# CONNECTORS.net
KiCad netlist of a schematic drawn in Altium Designer
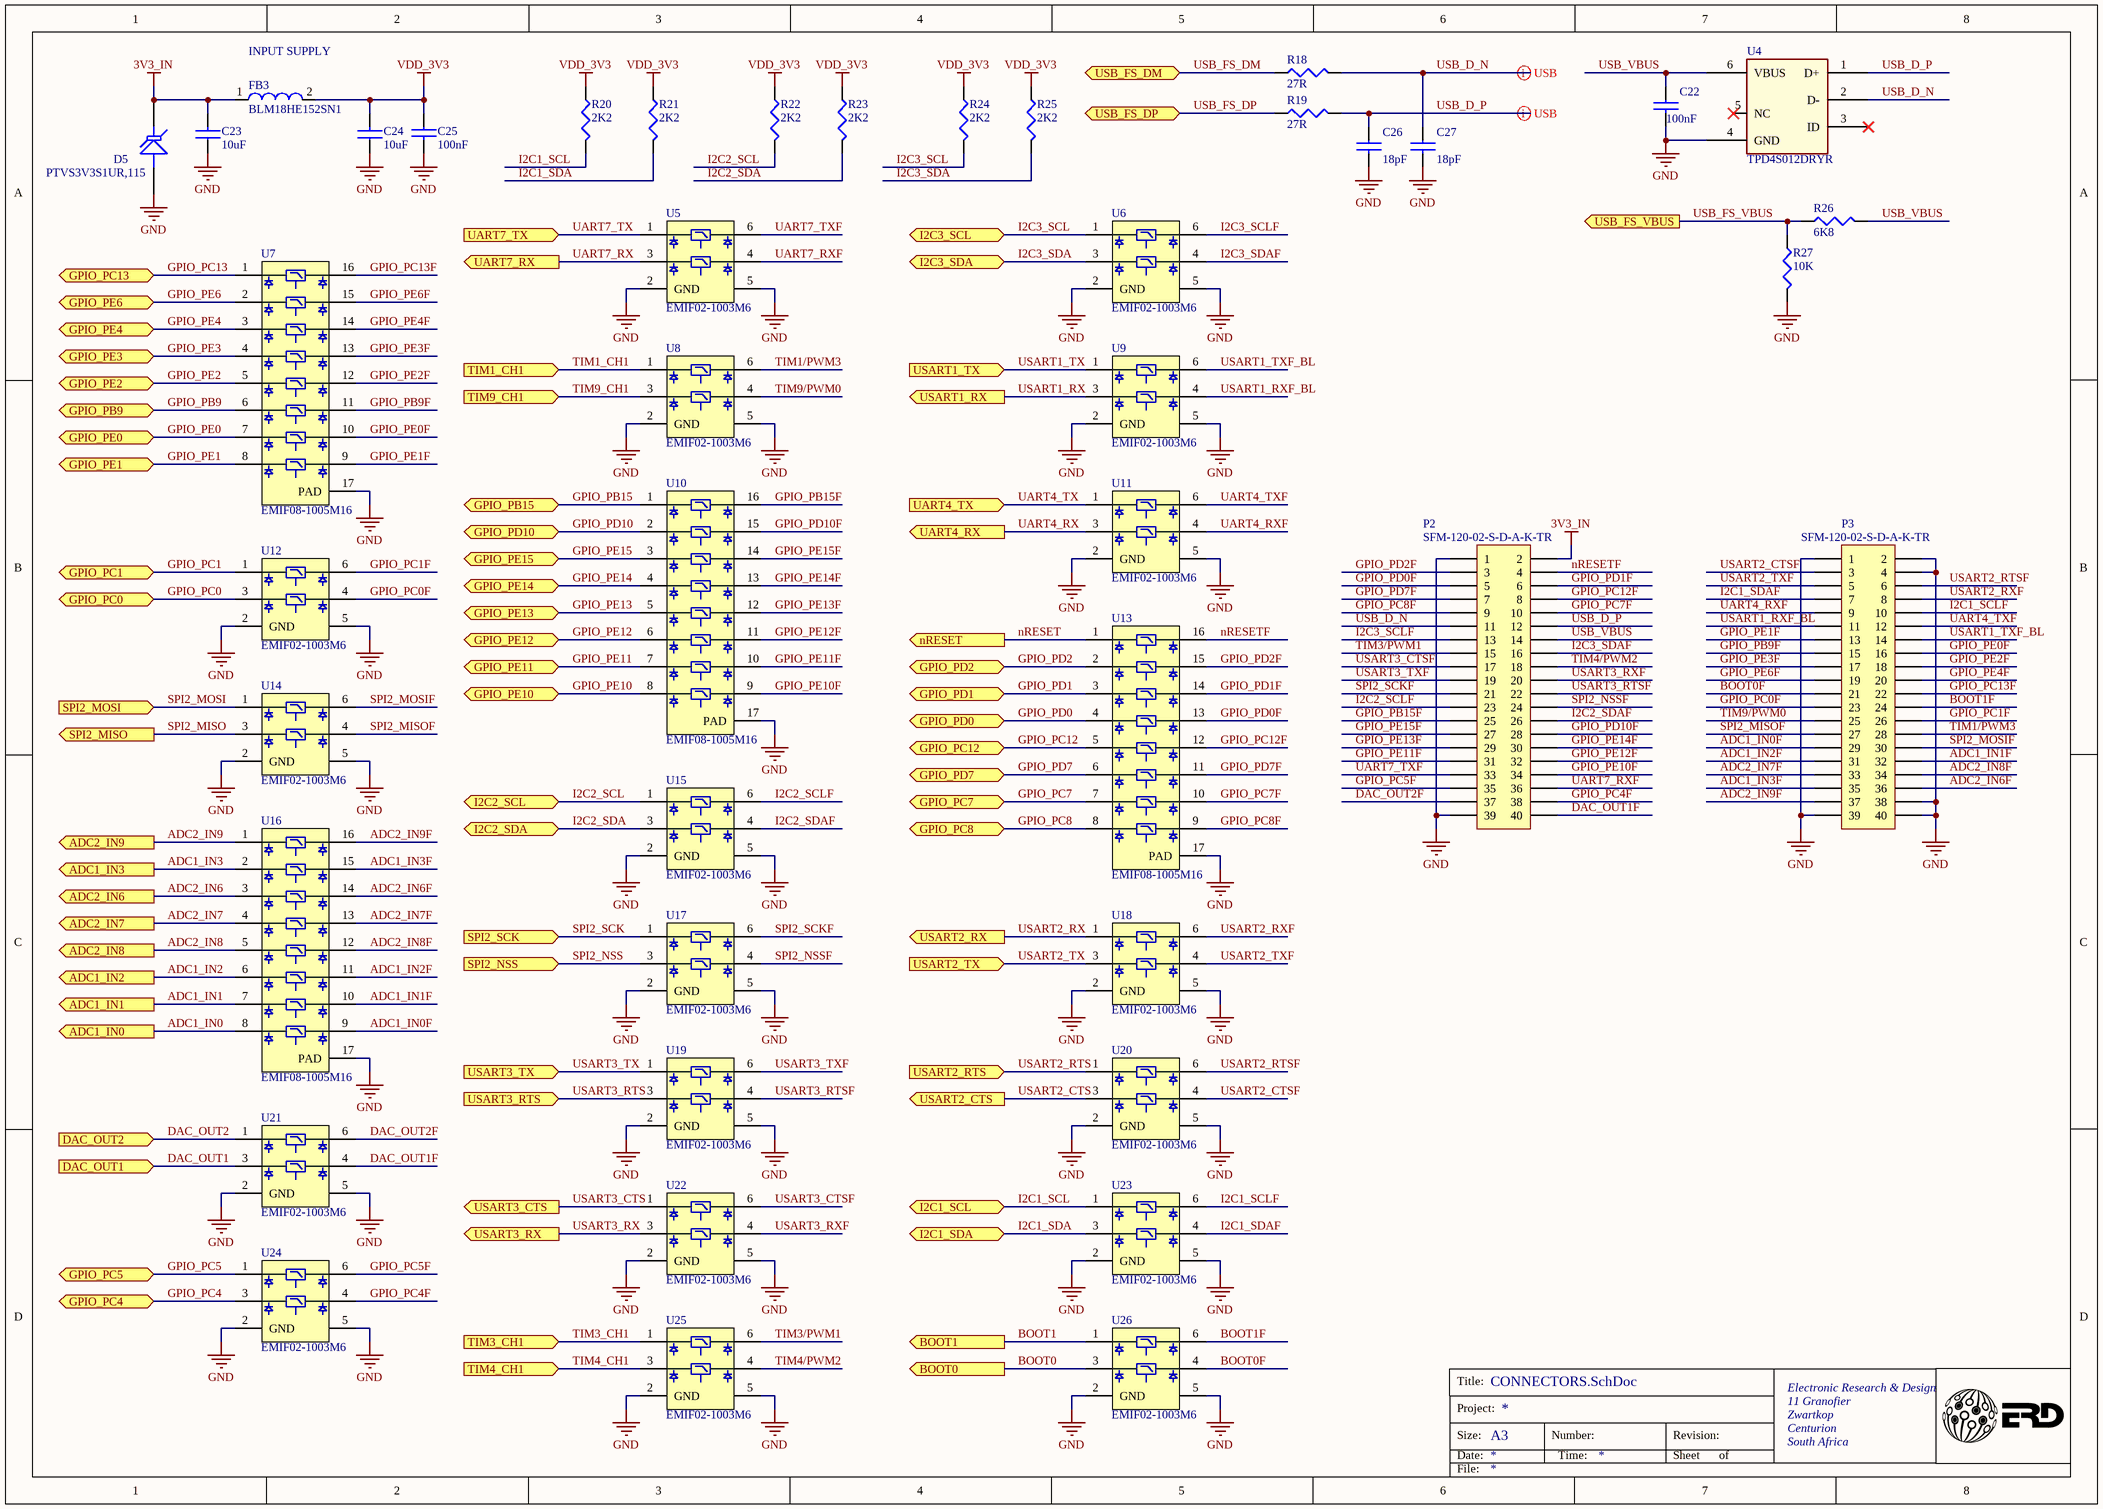
[diagram p0: CONNECTORS.SchDoc]

(export (version "E")
  (design (tool "Eeschema 10.0.6"))
  (components
    (comp (ref "C22")
      (value "100nF")
      (footprint "CC0402")
      (description "CAP CER 0.1UF 50V 10% X7R 0402")
      (fields (field (name "MANUFACTURER") "Murata") (field (name "PARTNUMBER") "GCM155R71H104KE02D"))
      (libsource (lib "ERD TiAm") (part "CAP CER 0.1UF 10V 10% X5R 0402"))
    )
    (comp (ref "C23")
      (value "10uF")
      (footprint "CC0603")
      (description "CAP CER 10UF 25V 20% X5R 0603")
      (fields (field (name "MANUFACTURER") "Murata") (field (name "PARTNUMBER") "GRM188R61E106MA73D"))
      (libsource (lib "ERD TiAm") (part "CAP CER 0.1UF 10V 10% X5R 0402"))
    )
    (comp (ref "C24")
      (value "10uF")
      (footprint "CC0603")
      (description "CAP CER 10UF 25V 20% X5R 0603")
      (fields (field (name "MANUFACTURER") "Murata") (field (name "PARTNUMBER") "GRM188R61E106MA73D"))
      (libsource (lib "ERD TiAm") (part "CAP CER 0.1UF 10V 10% X5R 0402"))
    )
    (comp (ref "C25")
      (value "100nF")
      (footprint "CC0402")
      (description "CAP CER 0.1UF 50V 10% X7R 0402")
      (fields (field (name "MANUFACTURER") "Murata") (field (name "PARTNUMBER") "GCM155R71H104KE02D"))
      (libsource (lib "ERD TiAm") (part "CAP CER 0.1UF 10V 10% X5R 0402"))
    )
    (comp (ref "C26")
      (value "18pF")
      (footprint "CC0402")
      (description "CAP CER 18pF 50V 5% C0G 0402")
      (fields (field (name "MANUFACTURER") "AVX") (field (name "PARTNUMBER") "GJM1555C1H180FB01D"))
      (libsource (lib "ERD TiAm") (part "CAP CER 2.2UF 6.3V 10% X5R 0402"))
    )
    (comp (ref "C27")
      (value "18pF")
      (footprint "CC0402")
      (description "CAP CER 18pF 50V 5% C0G 0402")
      (fields (field (name "MANUFACTURER") "AVX") (field (name "PARTNUMBER") "GJM1555C1H180FB01D"))
      (libsource (lib "ERD TiAm") (part "CAP CER 2.2UF 6.3V 10% X5R 0402"))
    )
    (comp (ref "D5")
      (value "PTVS3V3S1UR,115")
      (footprint "SOD123W")
      (description "TVS, 3V3")
      (libsource (lib "Miscellaneous Devices") (part "Tranzorb"))
    )
    (comp (ref "FB3")
      (value "BLM18HE152SN1")
      (footprint "LC0603")
      (description "FERRITE, 500mA, 500mOHM, 0603")
      (libsource (lib "BEAGLEBONEBLACK_REV A5B") (part "FER_180_200_0"))
    )
    (comp (ref "P2")
      (value "SFM-120-02-S-D-A-K-TR")
      (footprint "ERD TiAm:SFM-120-02-S-D-A-K-TR")
      (description "Receptacle, 40 POS, 1.27mm PITCH, SMD")
      (libsource (lib "Miscellaneous Connectors") (part "Header 20X2"))
    )
    (comp (ref "P3")
      (value "SFM-120-02-S-D-A-K-TR")
      (footprint "ERD TiAm:SFM-120-02-S-D-A-K-TR")
      (description "Receptacle, 40 POS, 1.27mm PITCH, SMD")
      (libsource (lib "Miscellaneous Connectors") (part "Header 20X2"))
    )
    (comp (ref "R18")
      (value "27R")
      (footprint "RC0402")
      (description "RES, 27 OHM, 1/16W, 1%, 0402")
      (fields (field (name "MANUFACTURER") "Yageo") (field (name "PARTNUMBER") "RC0402FR-0727RL"))
      (libsource (lib "ERD TiAm") (part "RES_10K_1/16W_1%_0402"))
    )
    (comp (ref "R19")
      (value "27R")
      (footprint "RC0402")
      (description "RES, 27 OHM, 1/16W, 1%, 0402")
      (fields (field (name "MANUFACTURER") "Yageo") (field (name "PARTNUMBER") "RC0402FR-0727RL"))
      (libsource (lib "ERD TiAm") (part "RES_10K_1/16W_1%_0402"))
    )
    (comp (ref "R20")
      (value "2K2")
      (footprint "RC0402")
      (description "RES, 2K2 OHM, 1/16W, 1%, 0402")
      (fields (field (name "MANUFACTURER") "Yageo") (field (name "PARTNUMBER") "RC0402FR-072K2L"))
      (libsource (lib "ERD TiAm") (part "RES_10K_1/16W_1%_0402"))
    )
    (comp (ref "R21")
      (value "2K2")
      (footprint "RC0402")
      (description "RES, 2K2 OHM, 1/16W, 1%, 0402")
      (fields (field (name "MANUFACTURER") "Yageo") (field (name "PARTNUMBER") "RC0402FR-072K2L"))
      (libsource (lib "ERD TiAm") (part "RES_10K_1/16W_1%_0402"))
    )
    (comp (ref "R22")
      (value "2K2")
      (footprint "RC0402")
      (description "RES, 2K2 OHM, 1/16W, 1%, 0402")
      (fields (field (name "MANUFACTURER") "Yageo") (field (name "PARTNUMBER") "RC0402FR-072K2L"))
      (libsource (lib "ERD TiAm") (part "RES_10K_1/16W_1%_0402"))
    )
    (comp (ref "R23")
      (value "2K2")
      (footprint "RC0402")
      (description "RES, 2K2 OHM, 1/16W, 1%, 0402")
      (fields (field (name "MANUFACTURER") "Yageo") (field (name "PARTNUMBER") "RC0402FR-072K2L"))
      (libsource (lib "ERD TiAm") (part "RES_10K_1/16W_1%_0402"))
    )
    (comp (ref "R24")
      (value "2K2")
      (footprint "RC0402")
      (description "RES, 2K2 OHM, 1/16W, 1%, 0402")
      (fields (field (name "MANUFACTURER") "Yageo") (field (name "PARTNUMBER") "RC0402FR-072K2L"))
      (libsource (lib "ERD TiAm") (part "RES_10K_1/16W_1%_0402"))
    )
    (comp (ref "R25")
      (value "2K2")
      (footprint "RC0402")
      (description "RES, 2K2 OHM, 1/16W, 1%, 0402")
      (fields (field (name "MANUFACTURER") "Yageo") (field (name "PARTNUMBER") "RC0402FR-072K2L"))
      (libsource (lib "ERD TiAm") (part "RES_10K_1/16W_1%_0402"))
    )
    (comp (ref "R26")
      (value "6K8")
      (footprint "RC0402")
      (description "RES, 6K8 OHM, 1/16W, 1%, 0402")
      (fields (field (name "MANUFACTURER") "Yageo") (field (name "PARTNUMBER") "RC0402FR-076K8L"))
      (libsource (lib "ERD TiAm") (part "RES_10K_1/16W_1%_0402"))
    )
    (comp (ref "R27")
      (value "10K")
      (footprint "RC0402")
      (description "RES, 10K OHM, 1/16W, 1%, 0402")
      (fields (field (name "MANUFACTURER") "Yageo") (field (name "PARTNUMBER") "RC0402FR-0710KL"))
      (libsource (lib "ERD TiAm") (part "RES_10K_1/16W_1%_0402"))
    )
    (comp (ref "U4")
      (value "TPD4S012DRYR")
      (footprint "U_6_DRY")
      (description "ESD 4channel USB Interface")
      (fields (field (name "MANUFACTURER") "Texas Instruments"))
      (libsource (lib "ERD TiAm") (part "PROT_TPD4S012"))
    )
    (comp (ref "U5")
      (value "EMIF02-1003M6")
      (footprint "uQFN-6L")
      (description "EMI Filter, ESD, uQFN-6")
      (libsource (lib "ERD TiAm") (part "EMIF02-1003M6"))
    )
    (comp (ref "U6")
      (value "EMIF02-1003M6")
      (footprint "uQFN-6L")
      (description "EMI Filter, ESD, uQFN-6")
      (libsource (lib "ERD TiAm") (part "EMIF02-1003M6"))
    )
    (comp (ref "U7")
      (value "EMIF08-1005M16")
      (footprint "QFN-16L")
      (description "EMI Filter, ESD, QFN-16L")
      (libsource (lib "ERD TiAm") (part "EMIF08-1005M16"))
    )
    (comp (ref "U8")
      (value "EMIF02-1003M6")
      (footprint "uQFN-6L")
      (description "EMI Filter, ESD, uQFN-6")
      (libsource (lib "ERD TiAm") (part "EMIF02-1003M6"))
    )
    (comp (ref "U9")
      (value "EMIF02-1003M6")
      (footprint "uQFN-6L")
      (description "EMI Filter, ESD, uQFN-6")
      (libsource (lib "ERD TiAm") (part "EMIF02-1003M6"))
    )
    (comp (ref "U10")
      (value "EMIF08-1005M16")
      (footprint "QFN-16L")
      (description "EMI Filter, ESD, QFN-16L")
      (libsource (lib "ERD TiAm") (part "EMIF08-1005M16"))
    )
    (comp (ref "U11")
      (value "EMIF02-1003M6")
      (footprint "uQFN-6L")
      (description "EMI Filter, ESD, uQFN-6")
      (libsource (lib "ERD TiAm") (part "EMIF02-1003M6"))
    )
    (comp (ref "U12")
      (value "EMIF02-1003M6")
      (footprint "uQFN-6L")
      (description "EMI Filter, ESD, uQFN-6")
      (libsource (lib "ERD TiAm") (part "EMIF02-1003M6"))
    )
    (comp (ref "U13")
      (value "EMIF08-1005M16")
      (footprint "QFN-16L")
      (description "EMI Filter, ESD, QFN-16L")
      (libsource (lib "ERD TiAm") (part "EMIF08-1005M16"))
    )
    (comp (ref "U14")
      (value "EMIF02-1003M6")
      (footprint "uQFN-6L")
      (description "EMI Filter, ESD, uQFN-6")
      (libsource (lib "ERD TiAm") (part "EMIF02-1003M6"))
    )
    (comp (ref "U15")
      (value "EMIF02-1003M6")
      (footprint "uQFN-6L")
      (description "EMI Filter, ESD, uQFN-6")
      (libsource (lib "ERD TiAm") (part "EMIF02-1003M6"))
    )
    (comp (ref "U16")
      (value "EMIF08-1005M16")
      (footprint "QFN-16L")
      (description "EMI Filter, ESD, QFN-16L")
      (libsource (lib "ERD TiAm") (part "EMIF08-1005M16"))
    )
    (comp (ref "U17")
      (value "EMIF02-1003M6")
      (footprint "uQFN-6L")
      (description "EMI Filter, ESD, uQFN-6")
      (libsource (lib "ERD TiAm") (part "EMIF02-1003M6"))
    )
    (comp (ref "U18")
      (value "EMIF02-1003M6")
      (footprint "uQFN-6L")
      (description "EMI Filter, ESD, uQFN-6")
      (libsource (lib "ERD TiAm") (part "EMIF02-1003M6"))
    )
    (comp (ref "U19")
      (value "EMIF02-1003M6")
      (footprint "uQFN-6L")
      (description "EMI Filter, ESD, uQFN-6")
      (libsource (lib "ERD TiAm") (part "EMIF02-1003M6"))
    )
    (comp (ref "U20")
      (value "EMIF02-1003M6")
      (footprint "uQFN-6L")
      (description "EMI Filter, ESD, uQFN-6")
      (libsource (lib "ERD TiAm") (part "EMIF02-1003M6"))
    )
    (comp (ref "U21")
      (value "EMIF02-1003M6")
      (footprint "uQFN-6L")
      (description "EMI Filter, ESD, uQFN-6")
      (libsource (lib "ERD TiAm") (part "EMIF02-1003M6"))
    )
    (comp (ref "U22")
      (value "EMIF02-1003M6")
      (footprint "uQFN-6L")
      (description "EMI Filter, ESD, uQFN-6")
      (libsource (lib "ERD TiAm") (part "EMIF02-1003M6"))
    )
    (comp (ref "U23")
      (value "EMIF02-1003M6")
      (footprint "uQFN-6L")
      (description "EMI Filter, ESD, uQFN-6")
      (libsource (lib "ERD TiAm") (part "EMIF02-1003M6"))
    )
    (comp (ref "U24")
      (value "EMIF02-1003M6")
      (footprint "uQFN-6L")
      (description "EMI Filter, ESD, uQFN-6")
      (libsource (lib "ERD TiAm") (part "EMIF02-1003M6"))
    )
    (comp (ref "U25")
      (value "EMIF02-1003M6")
      (footprint "uQFN-6L")
      (description "EMI Filter, ESD, uQFN-6")
      (libsource (lib "ERD TiAm") (part "EMIF02-1003M6"))
    )
    (comp (ref "U26")
      (value "EMIF02-1003M6")
      (footprint "uQFN-6L")
      (description "EMI Filter, ESD, uQFN-6")
      (libsource (lib "ERD TiAm") (part "EMIF02-1003M6"))
    )
  )
  (nets
    (net (code "1") (name "/ADC1_IN0") (class "Default")
      (node (ref "U16") (pin "8") (pinfunction "8_8") (pintype "passive"))
    )
    (net (code "2") (name "/ADC1_IN0F") (class "Default")
      (node (ref "P3") (pin "29") (pinfunction "29_29") (pintype "passive"))
      (node (ref "U16") (pin "9") (pinfunction "9_9") (pintype "passive"))
    )
    (net (code "3") (name "/ADC1_IN1") (class "Default")
      (node (ref "U16") (pin "7") (pinfunction "7_7") (pintype "passive"))
    )
    (net (code "4") (name "/ADC1_IN1F") (class "Default")
      (node (ref "P3") (pin "32") (pinfunction "32_32") (pintype "passive"))
      (node (ref "U16") (pin "10") (pinfunction "10_10") (pintype "passive"))
    )
    (net (code "5") (name "/ADC1_IN2") (class "Default")
      (node (ref "U16") (pin "6") (pinfunction "6_6") (pintype "passive"))
    )
    (net (code "6") (name "/ADC1_IN2F") (class "Default")
      (node (ref "P3") (pin "31") (pinfunction "31_31") (pintype "passive"))
      (node (ref "U16") (pin "11") (pinfunction "11_11") (pintype "passive"))
    )
    (net (code "7") (name "/ADC1_IN3") (class "Default")
      (node (ref "U16") (pin "2") (pinfunction "2_2") (pintype "passive"))
    )
    (net (code "8") (name "/ADC1_IN3F") (class "Default")
      (node (ref "P3") (pin "35") (pinfunction "35_35") (pintype "passive"))
      (node (ref "U16") (pin "15") (pinfunction "15_15") (pintype "passive"))
    )
    (net (code "9") (name "/ADC2_IN6") (class "Default")
      (node (ref "U16") (pin "3") (pinfunction "3_3") (pintype "passive"))
    )
    (net (code "10") (name "/ADC2_IN6F") (class "Default")
      (node (ref "P3") (pin "36") (pinfunction "36_36") (pintype "passive"))
      (node (ref "U16") (pin "14") (pinfunction "14_14") (pintype "passive"))
    )
    (net (code "11") (name "/ADC2_IN7") (class "Default")
      (node (ref "U16") (pin "4") (pinfunction "4_4") (pintype "passive"))
    )
    (net (code "12") (name "/ADC2_IN7F") (class "Default")
      (node (ref "P3") (pin "33") (pinfunction "33_33") (pintype "passive"))
      (node (ref "U16") (pin "13") (pinfunction "13_13") (pintype "passive"))
    )
    (net (code "13") (name "/ADC2_IN8") (class "Default")
      (node (ref "U16") (pin "5") (pinfunction "5_5") (pintype "passive"))
    )
    (net (code "14") (name "/ADC2_IN8F") (class "Default")
      (node (ref "P3") (pin "34") (pinfunction "34_34") (pintype "passive"))
      (node (ref "U16") (pin "12") (pinfunction "12_12") (pintype "passive"))
    )
    (net (code "15") (name "/ADC2_IN9") (class "Default")
      (node (ref "U16") (pin "1") (pinfunction "1_1") (pintype "passive"))
    )
    (net (code "16") (name "/ADC2_IN9F") (class "Default")
      (node (ref "P3") (pin "37") (pinfunction "37_37") (pintype "passive"))
      (node (ref "U16") (pin "16") (pinfunction "16_16") (pintype "passive"))
    )
    (net (code "17") (name "/BOOT0") (class "Default")
      (node (ref "U26") (pin "3") (pinfunction "3_3") (pintype "passive"))
    )
    (net (code "18") (name "/BOOT0F") (class "Default")
      (node (ref "P3") (pin "21") (pinfunction "21_21") (pintype "passive"))
      (node (ref "U26") (pin "4") (pinfunction "4_4") (pintype "passive"))
    )
    (net (code "19") (name "/BOOT1") (class "Default")
      (node (ref "U26") (pin "1") (pinfunction "1_1") (pintype "passive"))
    )
    (net (code "20") (name "/BOOT1F") (class "Default")
      (node (ref "P3") (pin "24") (pinfunction "24_24") (pintype "passive"))
      (node (ref "U26") (pin "6") (pinfunction "6_6") (pintype "passive"))
    )
    (net (code "21") (name "/DAC_OUT1") (class "Default")
      (node (ref "U21") (pin "3") (pinfunction "3_3") (pintype "passive"))
    )
    (net (code "22") (name "/DAC_OUT1F") (class "Default")
      (node (ref "P2") (pin "40") (pinfunction "40_40") (pintype "passive"))
      (node (ref "U21") (pin "4") (pinfunction "4_4") (pintype "passive"))
    )
    (net (code "23") (name "/DAC_OUT2") (class "Default")
      (node (ref "U21") (pin "1") (pinfunction "1_1") (pintype "passive"))
    )
    (net (code "24") (name "/DAC_OUT2F") (class "Default")
      (node (ref "P2") (pin "37") (pinfunction "37_37") (pintype "passive"))
      (node (ref "U21") (pin "6") (pinfunction "6_6") (pintype "passive"))
    )
    (net (code "25") (name "/GPIO_PB9") (class "Default")
      (node (ref "U7") (pin "6") (pinfunction "6_6") (pintype "passive"))
    )
    (net (code "26") (name "/GPIO_PB9F") (class "Default")
      (node (ref "P3") (pin "15") (pinfunction "15_15") (pintype "passive"))
      (node (ref "U7") (pin "11") (pinfunction "11_11") (pintype "passive"))
    )
    (net (code "27") (name "/GPIO_PB15") (class "Default")
      (node (ref "U10") (pin "1") (pinfunction "1_1") (pintype "passive"))
    )
    (net (code "28") (name "/GPIO_PB15F") (class "Default")
      (node (ref "P2") (pin "25") (pinfunction "25_25") (pintype "passive"))
      (node (ref "U10") (pin "16") (pinfunction "16_16") (pintype "passive"))
    )
    (net (code "29") (name "/GPIO_PC0") (class "Default")
      (node (ref "U12") (pin "3") (pinfunction "3_3") (pintype "passive"))
    )
    (net (code "30") (name "/GPIO_PC0F") (class "Default")
      (node (ref "P3") (pin "23") (pinfunction "23_23") (pintype "passive"))
      (node (ref "U12") (pin "4") (pinfunction "4_4") (pintype "passive"))
    )
    (net (code "31") (name "/GPIO_PC1") (class "Default")
      (node (ref "U12") (pin "1") (pinfunction "1_1") (pintype "passive"))
    )
    (net (code "32") (name "/GPIO_PC1F") (class "Default")
      (node (ref "P3") (pin "26") (pinfunction "26_26") (pintype "passive"))
      (node (ref "U12") (pin "6") (pinfunction "6_6") (pintype "passive"))
    )
    (net (code "33") (name "/GPIO_PC4") (class "Default")
      (node (ref "U24") (pin "3") (pinfunction "3_3") (pintype "passive"))
    )
    (net (code "34") (name "/GPIO_PC4F") (class "Default")
      (node (ref "P2") (pin "38") (pinfunction "38_38") (pintype "passive"))
      (node (ref "U24") (pin "4") (pinfunction "4_4") (pintype "passive"))
    )
    (net (code "35") (name "/GPIO_PC5") (class "Default")
      (node (ref "U24") (pin "1") (pinfunction "1_1") (pintype "passive"))
    )
    (net (code "36") (name "/GPIO_PC5F") (class "Default")
      (node (ref "P2") (pin "35") (pinfunction "35_35") (pintype "passive"))
      (node (ref "U24") (pin "6") (pinfunction "6_6") (pintype "passive"))
    )
    (net (code "37") (name "/GPIO_PC7") (class "Default")
      (node (ref "U13") (pin "7") (pinfunction "7_7") (pintype "passive"))
    )
    (net (code "38") (name "/GPIO_PC7F") (class "Default")
      (node (ref "P2") (pin "10") (pinfunction "10_10") (pintype "passive"))
      (node (ref "U13") (pin "10") (pinfunction "10_10") (pintype "passive"))
    )
    (net (code "39") (name "/GPIO_PC8") (class "Default")
      (node (ref "U13") (pin "8") (pinfunction "8_8") (pintype "passive"))
    )
    (net (code "40") (name "/GPIO_PC8F") (class "Default")
      (node (ref "P2") (pin "9") (pinfunction "9_9") (pintype "passive"))
      (node (ref "U13") (pin "9") (pinfunction "9_9") (pintype "passive"))
    )
    (net (code "41") (name "/GPIO_PC12") (class "Default")
      (node (ref "U13") (pin "5") (pinfunction "5_5") (pintype "passive"))
    )
    (net (code "42") (name "/GPIO_PC12F") (class "Default")
      (node (ref "P2") (pin "8") (pinfunction "8_8") (pintype "passive"))
      (node (ref "U13") (pin "12") (pinfunction "12_12") (pintype "passive"))
    )
    (net (code "43") (name "/GPIO_PC13") (class "Default")
      (node (ref "U7") (pin "1") (pinfunction "1_1") (pintype "passive"))
    )
    (net (code "44") (name "/GPIO_PC13F") (class "Default")
      (node (ref "P3") (pin "22") (pinfunction "22_22") (pintype "passive"))
      (node (ref "U7") (pin "16") (pinfunction "16_16") (pintype "passive"))
    )
    (net (code "45") (name "/GPIO_PD0") (class "Default")
      (node (ref "U13") (pin "4") (pinfunction "4_4") (pintype "passive"))
    )
    (net (code "46") (name "/GPIO_PD0F") (class "Default")
      (node (ref "P2") (pin "5") (pinfunction "5_5") (pintype "passive"))
      (node (ref "U13") (pin "13") (pinfunction "13_13") (pintype "passive"))
    )
    (net (code "47") (name "/GPIO_PD1") (class "Default")
      (node (ref "U13") (pin "3") (pinfunction "3_3") (pintype "passive"))
    )
    (net (code "48") (name "/GPIO_PD1F") (class "Default")
      (node (ref "P2") (pin "6") (pinfunction "6_6") (pintype "passive"))
      (node (ref "U13") (pin "14") (pinfunction "14_14") (pintype "passive"))
    )
    (net (code "49") (name "/GPIO_PD2") (class "Default")
      (node (ref "U13") (pin "2") (pinfunction "2_2") (pintype "passive"))
    )
    (net (code "50") (name "/GPIO_PD2F") (class "Default")
      (node (ref "P2") (pin "3") (pinfunction "3_3") (pintype "passive"))
      (node (ref "U13") (pin "15") (pinfunction "15_15") (pintype "passive"))
    )
    (net (code "51") (name "/GPIO_PD7") (class "Default")
      (node (ref "U13") (pin "6") (pinfunction "6_6") (pintype "passive"))
    )
    (net (code "52") (name "/GPIO_PD7F") (class "Default")
      (node (ref "P2") (pin "7") (pinfunction "7_7") (pintype "passive"))
      (node (ref "U13") (pin "11") (pinfunction "11_11") (pintype "passive"))
    )
    (net (code "53") (name "/GPIO_PD10") (class "Default")
      (node (ref "U10") (pin "2") (pinfunction "2_2") (pintype "passive"))
    )
    (net (code "54") (name "/GPIO_PD10F") (class "Default")
      (node (ref "P2") (pin "28") (pinfunction "28_28") (pintype "passive"))
      (node (ref "U10") (pin "15") (pinfunction "15_15") (pintype "passive"))
    )
    (net (code "55") (name "/GPIO_PE0") (class "Default")
      (node (ref "U7") (pin "7") (pinfunction "7_7") (pintype "passive"))
    )
    (net (code "56") (name "/GPIO_PE0F") (class "Default")
      (node (ref "P3") (pin "16") (pinfunction "16_16") (pintype "passive"))
      (node (ref "U7") (pin "10") (pinfunction "10_10") (pintype "passive"))
    )
    (net (code "57") (name "/GPIO_PE1") (class "Default")
      (node (ref "U7") (pin "8") (pinfunction "8_8") (pintype "passive"))
    )
    (net (code "58") (name "/GPIO_PE1F") (class "Default")
      (node (ref "P3") (pin "13") (pinfunction "13_13") (pintype "passive"))
      (node (ref "U7") (pin "9") (pinfunction "9_9") (pintype "passive"))
    )
    (net (code "59") (name "/GPIO_PE2") (class "Default")
      (node (ref "U7") (pin "5") (pinfunction "5_5") (pintype "passive"))
    )
    (net (code "60") (name "/GPIO_PE2F") (class "Default")
      (node (ref "P3") (pin "18") (pinfunction "18_18") (pintype "passive"))
      (node (ref "U7") (pin "12") (pinfunction "12_12") (pintype "passive"))
    )
    (net (code "61") (name "/GPIO_PE3") (class "Default")
      (node (ref "U7") (pin "4") (pinfunction "4_4") (pintype "passive"))
    )
    (net (code "62") (name "/GPIO_PE3F") (class "Default")
      (node (ref "P3") (pin "17") (pinfunction "17_17") (pintype "passive"))
      (node (ref "U7") (pin "13") (pinfunction "13_13") (pintype "passive"))
    )
    (net (code "63") (name "/GPIO_PE4") (class "Default")
      (node (ref "U7") (pin "3") (pinfunction "3_3") (pintype "passive"))
    )
    (net (code "64") (name "/GPIO_PE4F") (class "Default")
      (node (ref "P3") (pin "20") (pinfunction "20_20") (pintype "passive"))
      (node (ref "U7") (pin "14") (pinfunction "14_14") (pintype "passive"))
    )
    (net (code "65") (name "/GPIO_PE6") (class "Default")
      (node (ref "U7") (pin "2") (pinfunction "2_2") (pintype "passive"))
    )
    (net (code "66") (name "/GPIO_PE6F") (class "Default")
      (node (ref "P3") (pin "19") (pinfunction "19_19") (pintype "passive"))
      (node (ref "U7") (pin "15") (pinfunction "15_15") (pintype "passive"))
    )
    (net (code "67") (name "/GPIO_PE10") (class "Default")
      (node (ref "U10") (pin "8") (pinfunction "8_8") (pintype "passive"))
    )
    (net (code "68") (name "/GPIO_PE10F") (class "Default")
      (node (ref "P2") (pin "34") (pinfunction "34_34") (pintype "passive"))
      (node (ref "U10") (pin "9") (pinfunction "9_9") (pintype "passive"))
    )
    (net (code "69") (name "/GPIO_PE11") (class "Default")
      (node (ref "U10") (pin "7") (pinfunction "7_7") (pintype "passive"))
    )
    (net (code "70") (name "/GPIO_PE11F") (class "Default")
      (node (ref "P2") (pin "31") (pinfunction "31_31") (pintype "passive"))
      (node (ref "U10") (pin "10") (pinfunction "10_10") (pintype "passive"))
    )
    (net (code "71") (name "/GPIO_PE12") (class "Default")
      (node (ref "U10") (pin "6") (pinfunction "6_6") (pintype "passive"))
    )
    (net (code "72") (name "/GPIO_PE12F") (class "Default")
      (node (ref "P2") (pin "32") (pinfunction "32_32") (pintype "passive"))
      (node (ref "U10") (pin "11") (pinfunction "11_11") (pintype "passive"))
    )
    (net (code "73") (name "/GPIO_PE13") (class "Default")
      (node (ref "U10") (pin "5") (pinfunction "5_5") (pintype "passive"))
    )
    (net (code "74") (name "/GPIO_PE13F") (class "Default")
      (node (ref "P2") (pin "29") (pinfunction "29_29") (pintype "passive"))
      (node (ref "U10") (pin "12") (pinfunction "12_12") (pintype "passive"))
    )
    (net (code "75") (name "/GPIO_PE14") (class "Default")
      (node (ref "U10") (pin "4") (pinfunction "4_4") (pintype "passive"))
    )
    (net (code "76") (name "/GPIO_PE14F") (class "Default")
      (node (ref "P2") (pin "30") (pinfunction "30_30") (pintype "passive"))
      (node (ref "U10") (pin "13") (pinfunction "13_13") (pintype "passive"))
    )
    (net (code "77") (name "/GPIO_PE15") (class "Default")
      (node (ref "U10") (pin "3") (pinfunction "3_3") (pintype "passive"))
    )
    (net (code "78") (name "/GPIO_PE15F") (class "Default")
      (node (ref "P2") (pin "27") (pinfunction "27_27") (pintype "passive"))
      (node (ref "U10") (pin "14") (pinfunction "14_14") (pintype "passive"))
    )
    (net (code "79") (name "/I2C1_SCL") (class "Default")
      (node (ref "R20") (pin "2") (pinfunction "2_2") (pintype "passive"))
      (node (ref "U23") (pin "1") (pinfunction "1_1") (pintype "passive"))
    )
    (net (code "80") (name "/I2C1_SCLF") (class "Default")
      (node (ref "P3") (pin "10") (pinfunction "10_10") (pintype "passive"))
      (node (ref "U23") (pin "6") (pinfunction "6_6") (pintype "passive"))
    )
    (net (code "81") (name "/I2C1_SDA") (class "Default")
      (node (ref "R21") (pin "2") (pinfunction "2_2") (pintype "passive"))
      (node (ref "U23") (pin "3") (pinfunction "3_3") (pintype "passive"))
    )
    (net (code "82") (name "/I2C1_SDAF") (class "Default")
      (node (ref "P3") (pin "7") (pinfunction "7_7") (pintype "passive"))
      (node (ref "U23") (pin "4") (pinfunction "4_4") (pintype "passive"))
    )
    (net (code "83") (name "/I2C2_SCL") (class "Default")
      (node (ref "R22") (pin "2") (pinfunction "2_2") (pintype "passive"))
      (node (ref "U15") (pin "1") (pinfunction "1_1") (pintype "passive"))
    )
    (net (code "84") (name "/I2C2_SCLF") (class "Default")
      (node (ref "P2") (pin "23") (pinfunction "23_23") (pintype "passive"))
      (node (ref "U15") (pin "6") (pinfunction "6_6") (pintype "passive"))
    )
    (net (code "85") (name "/I2C2_SDA") (class "Default")
      (node (ref "R23") (pin "2") (pinfunction "2_2") (pintype "passive"))
      (node (ref "U15") (pin "3") (pinfunction "3_3") (pintype "passive"))
    )
    (net (code "86") (name "/I2C2_SDAF") (class "Default")
      (node (ref "P2") (pin "26") (pinfunction "26_26") (pintype "passive"))
      (node (ref "U15") (pin "4") (pinfunction "4_4") (pintype "passive"))
    )
    (net (code "87") (name "/I2C3_SCL") (class "Default")
      (node (ref "R24") (pin "2") (pinfunction "2_2") (pintype "passive"))
      (node (ref "U6") (pin "1") (pinfunction "1_1") (pintype "passive"))
    )
    (net (code "88") (name "/I2C3_SCLF") (class "Default")
      (node (ref "P2") (pin "13") (pinfunction "13_13") (pintype "passive"))
      (node (ref "U6") (pin "6") (pinfunction "6_6") (pintype "passive"))
    )
    (net (code "89") (name "/I2C3_SDA") (class "Default")
      (node (ref "R25") (pin "2") (pinfunction "2_2") (pintype "passive"))
      (node (ref "U6") (pin "3") (pinfunction "3_3") (pintype "passive"))
    )
    (net (code "90") (name "/I2C3_SDAF") (class "Default")
      (node (ref "P2") (pin "16") (pinfunction "16_16") (pintype "passive"))
      (node (ref "U6") (pin "4") (pinfunction "4_4") (pintype "passive"))
    )
    (net (code "91") (name "/SPI2_MISO") (class "Default")
      (node (ref "U14") (pin "3") (pinfunction "3_3") (pintype "passive"))
    )
    (net (code "92") (name "/SPI2_MISOF") (class "Default")
      (node (ref "P3") (pin "27") (pinfunction "27_27") (pintype "passive"))
      (node (ref "U14") (pin "4") (pinfunction "4_4") (pintype "passive"))
    )
    (net (code "93") (name "/SPI2_MOSI") (class "Default")
      (node (ref "U14") (pin "1") (pinfunction "1_1") (pintype "passive"))
    )
    (net (code "94") (name "/SPI2_MOSIF") (class "Default")
      (node (ref "P3") (pin "30") (pinfunction "30_30") (pintype "passive"))
      (node (ref "U14") (pin "6") (pinfunction "6_6") (pintype "passive"))
    )
    (net (code "95") (name "/SPI2_NSS") (class "Default")
      (node (ref "U17") (pin "3") (pinfunction "3_3") (pintype "passive"))
    )
    (net (code "96") (name "/SPI2_NSSF") (class "Default")
      (node (ref "P2") (pin "24") (pinfunction "24_24") (pintype "passive"))
      (node (ref "U17") (pin "4") (pinfunction "4_4") (pintype "passive"))
    )
    (net (code "97") (name "/SPI2_SCK") (class "Default")
      (node (ref "U17") (pin "1") (pinfunction "1_1") (pintype "passive"))
    )
    (net (code "98") (name "/SPI2_SCKF") (class "Default")
      (node (ref "P2") (pin "21") (pinfunction "21_21") (pintype "passive"))
      (node (ref "U17") (pin "6") (pinfunction "6_6") (pintype "passive"))
    )
    (net (code "99") (name "/TIM1_CH1") (class "Default")
      (node (ref "U8") (pin "1") (pinfunction "1_1") (pintype "passive"))
    )
    (net (code "100") (name "/TIM1{slash}PWM3") (class "Default")
      (node (ref "P3") (pin "28") (pinfunction "28_28") (pintype "passive"))
      (node (ref "U8") (pin "6") (pinfunction "6_6") (pintype "passive"))
    )
    (net (code "101") (name "/TIM3_CH1") (class "Default")
      (node (ref "U25") (pin "1") (pinfunction "1_1") (pintype "passive"))
    )
    (net (code "102") (name "/TIM3{slash}PWM1") (class "Default")
      (node (ref "P2") (pin "15") (pinfunction "15_15") (pintype "passive"))
      (node (ref "U25") (pin "6") (pinfunction "6_6") (pintype "passive"))
    )
    (net (code "103") (name "/TIM4_CH1") (class "Default")
      (node (ref "U25") (pin "3") (pinfunction "3_3") (pintype "passive"))
    )
    (net (code "104") (name "/TIM4{slash}PWM2") (class "Default")
      (node (ref "P2") (pin "18") (pinfunction "18_18") (pintype "passive"))
      (node (ref "U25") (pin "4") (pinfunction "4_4") (pintype "passive"))
    )
    (net (code "105") (name "/TIM9_CH1") (class "Default")
      (node (ref "U8") (pin "3") (pinfunction "3_3") (pintype "passive"))
    )
    (net (code "106") (name "/TIM9{slash}PWM0") (class "Default")
      (node (ref "P3") (pin "25") (pinfunction "25_25") (pintype "passive"))
      (node (ref "U8") (pin "4") (pinfunction "4_4") (pintype "passive"))
    )
    (net (code "107") (name "/UART4_RX") (class "Default")
      (node (ref "U11") (pin "3") (pinfunction "3_3") (pintype "passive"))
    )
    (net (code "108") (name "/UART4_RXF") (class "Default")
      (node (ref "P3") (pin "9") (pinfunction "9_9") (pintype "passive"))
      (node (ref "U11") (pin "4") (pinfunction "4_4") (pintype "passive"))
    )
    (net (code "109") (name "/UART4_TX") (class "Default")
      (node (ref "U11") (pin "1") (pinfunction "1_1") (pintype "passive"))
    )
    (net (code "110") (name "/UART4_TXF") (class "Default")
      (node (ref "P3") (pin "12") (pinfunction "12_12") (pintype "passive"))
      (node (ref "U11") (pin "6") (pinfunction "6_6") (pintype "passive"))
    )
    (net (code "111") (name "/UART7_RX") (class "Default")
      (node (ref "U5") (pin "3") (pinfunction "3_3") (pintype "passive"))
    )
    (net (code "112") (name "/UART7_RXF") (class "Default")
      (node (ref "P2") (pin "36") (pinfunction "36_36") (pintype "passive"))
      (node (ref "U5") (pin "4") (pinfunction "4_4") (pintype "passive"))
    )
    (net (code "113") (name "/UART7_TX") (class "Default")
      (node (ref "U5") (pin "1") (pinfunction "1_1") (pintype "passive"))
    )
    (net (code "114") (name "/UART7_TXF") (class "Default")
      (node (ref "P2") (pin "33") (pinfunction "33_33") (pintype "passive"))
      (node (ref "U5") (pin "6") (pinfunction "6_6") (pintype "passive"))
    )
    (net (code "115") (name "/USART1_RX") (class "Default")
      (node (ref "U9") (pin "3") (pinfunction "3_3") (pintype "passive"))
    )
    (net (code "116") (name "/USART1_RXF_BL") (class "Default")
      (node (ref "P3") (pin "11") (pinfunction "11_11") (pintype "passive"))
      (node (ref "U9") (pin "4") (pinfunction "4_4") (pintype "passive"))
    )
    (net (code "117") (name "/USART1_TX") (class "Default")
      (node (ref "U9") (pin "1") (pinfunction "1_1") (pintype "passive"))
    )
    (net (code "118") (name "/USART1_TXF_BL") (class "Default")
      (node (ref "P3") (pin "14") (pinfunction "14_14") (pintype "passive"))
      (node (ref "U9") (pin "6") (pinfunction "6_6") (pintype "passive"))
    )
    (net (code "119") (name "/USART2_CTS") (class "Default")
      (node (ref "U20") (pin "3") (pinfunction "3_3") (pintype "passive"))
    )
    (net (code "120") (name "/USART2_CTSF") (class "Default")
      (node (ref "P3") (pin "3") (pinfunction "3_3") (pintype "passive"))
      (node (ref "U20") (pin "4") (pinfunction "4_4") (pintype "passive"))
    )
    (net (code "121") (name "/USART2_RTS") (class "Default")
      (node (ref "U20") (pin "1") (pinfunction "1_1") (pintype "passive"))
    )
    (net (code "122") (name "/USART2_RTSF") (class "Default")
      (node (ref "P3") (pin "6") (pinfunction "6_6") (pintype "passive"))
      (node (ref "U20") (pin "6") (pinfunction "6_6") (pintype "passive"))
    )
    (net (code "123") (name "/USART2_RX") (class "Default")
      (node (ref "U18") (pin "1") (pinfunction "1_1") (pintype "passive"))
    )
    (net (code "124") (name "/USART2_RXF") (class "Default")
      (node (ref "P3") (pin "8") (pinfunction "8_8") (pintype "passive"))
      (node (ref "U18") (pin "6") (pinfunction "6_6") (pintype "passive"))
    )
    (net (code "125") (name "/USART2_TX") (class "Default")
      (node (ref "U18") (pin "3") (pinfunction "3_3") (pintype "passive"))
    )
    (net (code "126") (name "/USART2_TXF") (class "Default")
      (node (ref "P3") (pin "5") (pinfunction "5_5") (pintype "passive"))
      (node (ref "U18") (pin "4") (pinfunction "4_4") (pintype "passive"))
    )
    (net (code "127") (name "/USART3_CTS") (class "Default")
      (node (ref "U22") (pin "1") (pinfunction "1_1") (pintype "passive"))
    )
    (net (code "128") (name "/USART3_CTSF") (class "Default")
      (node (ref "P2") (pin "17") (pinfunction "17_17") (pintype "passive"))
      (node (ref "U22") (pin "6") (pinfunction "6_6") (pintype "passive"))
    )
    (net (code "129") (name "/USART3_RTS") (class "Default")
      (node (ref "U19") (pin "3") (pinfunction "3_3") (pintype "passive"))
    )
    (net (code "130") (name "/USART3_RTSF") (class "Default")
      (node (ref "P2") (pin "22") (pinfunction "22_22") (pintype "passive"))
      (node (ref "U19") (pin "4") (pinfunction "4_4") (pintype "passive"))
    )
    (net (code "131") (name "/USART3_RX") (class "Default")
      (node (ref "U22") (pin "3") (pinfunction "3_3") (pintype "passive"))
    )
    (net (code "132") (name "/USART3_RXF") (class "Default")
      (node (ref "P2") (pin "20") (pinfunction "20_20") (pintype "passive"))
      (node (ref "U22") (pin "4") (pinfunction "4_4") (pintype "passive"))
    )
    (net (code "133") (name "/USART3_TX") (class "Default")
      (node (ref "U19") (pin "1") (pinfunction "1_1") (pintype "passive"))
    )
    (net (code "134") (name "/USART3_TXF") (class "Default")
      (node (ref "P2") (pin "19") (pinfunction "19_19") (pintype "passive"))
      (node (ref "U19") (pin "6") (pinfunction "6_6") (pintype "passive"))
    )
    (net (code "135") (name "/USB_D_N") (class "Default")
      (node (ref "C27") (pin "1") (pinfunction "1_1") (pintype "passive"))
      (node (ref "P2") (pin "11") (pinfunction "11_11") (pintype "passive"))
      (node (ref "R18") (pin "2") (pinfunction "2_2") (pintype "passive"))
      (node (ref "U4") (pin "2") (pinfunction "D-_2") (pintype "passive"))
    )
    (net (code "136") (name "/USB_D_P") (class "Default")
      (node (ref "C26") (pin "1") (pinfunction "1_1") (pintype "passive"))
      (node (ref "P2") (pin "12") (pinfunction "12_12") (pintype "passive"))
      (node (ref "R19") (pin "2") (pinfunction "2_2") (pintype "passive"))
      (node (ref "U4") (pin "1") (pinfunction "D+_1") (pintype "passive"))
    )
    (net (code "137") (name "/USB_FS_DM") (class "Default")
      (node (ref "R18") (pin "1") (pinfunction "1_1") (pintype "passive"))
    )
    (net (code "138") (name "/USB_FS_DP") (class "Default")
      (node (ref "R19") (pin "1") (pinfunction "1_1") (pintype "passive"))
    )
    (net (code "139") (name "/USB_FS_VBUS") (class "Default")
      (node (ref "R26") (pin "1") (pinfunction "1_1") (pintype "passive"))
      (node (ref "R27") (pin "1") (pinfunction "1_1") (pintype "passive"))
    )
    (net (code "140") (name "/USB_VBUS") (class "Default")
      (node (ref "C22") (pin "1") (pinfunction "1_1") (pintype "passive"))
      (node (ref "P2") (pin "14") (pinfunction "14_14") (pintype "passive"))
      (node (ref "R26") (pin "2") (pinfunction "2_2") (pintype "passive"))
      (node (ref "U4") (pin "6") (pinfunction "VBUS_6") (pintype "power_in"))
    )
    (net (code "141") (name "/nRESET") (class "Default")
      (node (ref "U13") (pin "1") (pinfunction "1_1") (pintype "passive"))
    )
    (net (code "142") (name "/nRESETF") (class "Default")
      (node (ref "P2") (pin "4") (pinfunction "4_4") (pintype "passive"))
      (node (ref "U13") (pin "16") (pinfunction "16_16") (pintype "passive"))
    )
    (net (code "143") (name "3V3_IN") (class "Default")
      (node (ref "C23") (pin "2") (pinfunction "2_2") (pintype "passive"))
      (node (ref "D5") (pin "1") (pinfunction "1_1") (pintype "passive"))
      (node (ref "FB3") (pin "1") (pinfunction "1_1") (pintype "passive"))
      (node (ref "P2") (pin "2") (pinfunction "2_2") (pintype "passive"))
    )
    (net (code "144") (name "GND") (class "Default")
      (node (ref "C22") (pin "2") (pinfunction "2_2") (pintype "passive"))
      (node (ref "C23") (pin "1") (pinfunction "1_1") (pintype "passive"))
      (node (ref "C24") (pin "1") (pinfunction "1_1") (pintype "passive"))
      (node (ref "C25") (pin "2") (pinfunction "2_2") (pintype "passive"))
      (node (ref "C26") (pin "2") (pinfunction "2_2") (pintype "passive"))
      (node (ref "C27") (pin "2") (pinfunction "2_2") (pintype "passive"))
      (node (ref "D5") (pin "2") (pinfunction "2_2") (pintype "passive"))
      (node (ref "P2") (pin "1") (pinfunction "1_1") (pintype "passive"))
      (node (ref "P2") (pin "39") (pinfunction "39_39") (pintype "passive"))
      (node (ref "P3") (pin "1") (pinfunction "1_1") (pintype "passive"))
      (node (ref "P3") (pin "2") (pinfunction "2_2") (pintype "passive"))
      (node (ref "P3") (pin "38") (pinfunction "38_38") (pintype "passive"))
      (node (ref "P3") (pin "39") (pinfunction "39_39") (pintype "passive"))
      (node (ref "P3") (pin "4") (pinfunction "4_4") (pintype "passive"))
      (node (ref "P3") (pin "40") (pinfunction "40_40") (pintype "passive"))
      (node (ref "R27") (pin "2") (pinfunction "2_2") (pintype "passive"))
      (node (ref "U10") (pin "17") (pinfunction "PAD_17") (pintype "passive"))
      (node (ref "U11") (pin "2") (pinfunction "GND_2") (pintype "passive"))
      (node (ref "U11") (pin "5") (pinfunction "GND_5") (pintype "passive"))
      (node (ref "U12") (pin "2") (pinfunction "GND_2") (pintype "passive"))
      (node (ref "U12") (pin "5") (pinfunction "GND_5") (pintype "passive"))
      (node (ref "U13") (pin "17") (pinfunction "PAD_17") (pintype "passive"))
      (node (ref "U14") (pin "2") (pinfunction "GND_2") (pintype "passive"))
      (node (ref "U14") (pin "5") (pinfunction "GND_5") (pintype "passive"))
      (node (ref "U15") (pin "2") (pinfunction "GND_2") (pintype "passive"))
      (node (ref "U15") (pin "5") (pinfunction "GND_5") (pintype "passive"))
      (node (ref "U16") (pin "17") (pinfunction "PAD_17") (pintype "passive"))
      (node (ref "U17") (pin "2") (pinfunction "GND_2") (pintype "passive"))
      (node (ref "U17") (pin "5") (pinfunction "GND_5") (pintype "passive"))
      (node (ref "U18") (pin "2") (pinfunction "GND_2") (pintype "passive"))
      (node (ref "U18") (pin "5") (pinfunction "GND_5") (pintype "passive"))
      (node (ref "U19") (pin "2") (pinfunction "GND_2") (pintype "passive"))
      (node (ref "U19") (pin "5") (pinfunction "GND_5") (pintype "passive"))
      (node (ref "U20") (pin "2") (pinfunction "GND_2") (pintype "passive"))
      (node (ref "U20") (pin "5") (pinfunction "GND_5") (pintype "passive"))
      (node (ref "U21") (pin "2") (pinfunction "GND_2") (pintype "passive"))
      (node (ref "U21") (pin "5") (pinfunction "GND_5") (pintype "passive"))
      (node (ref "U22") (pin "2") (pinfunction "GND_2") (pintype "passive"))
      (node (ref "U22") (pin "5") (pinfunction "GND_5") (pintype "passive"))
      (node (ref "U23") (pin "2") (pinfunction "GND_2") (pintype "passive"))
      (node (ref "U23") (pin "5") (pinfunction "GND_5") (pintype "passive"))
      (node (ref "U24") (pin "2") (pinfunction "GND_2") (pintype "passive"))
      (node (ref "U24") (pin "5") (pinfunction "GND_5") (pintype "passive"))
      (node (ref "U25") (pin "2") (pinfunction "GND_2") (pintype "passive"))
      (node (ref "U25") (pin "5") (pinfunction "GND_5") (pintype "passive"))
      (node (ref "U26") (pin "2") (pinfunction "GND_2") (pintype "passive"))
      (node (ref "U26") (pin "5") (pinfunction "GND_5") (pintype "passive"))
      (node (ref "U4") (pin "4") (pinfunction "GND_4") (pintype "power_in"))
      (node (ref "U5") (pin "2") (pinfunction "GND_2") (pintype "passive"))
      (node (ref "U5") (pin "5") (pinfunction "GND_5") (pintype "passive"))
      (node (ref "U6") (pin "2") (pinfunction "GND_2") (pintype "passive"))
      (node (ref "U6") (pin "5") (pinfunction "GND_5") (pintype "passive"))
      (node (ref "U7") (pin "17") (pinfunction "PAD_17") (pintype "passive"))
      (node (ref "U8") (pin "2") (pinfunction "GND_2") (pintype "passive"))
      (node (ref "U8") (pin "5") (pinfunction "GND_5") (pintype "passive"))
      (node (ref "U9") (pin "2") (pinfunction "GND_2") (pintype "passive"))
      (node (ref "U9") (pin "5") (pinfunction "GND_5") (pintype "passive"))
    )
    (net (code "145") (name "VDD_3V3") (class "Default")
      (node (ref "C24") (pin "2") (pinfunction "2_2") (pintype "passive"))
      (node (ref "C25") (pin "1") (pinfunction "1_1") (pintype "passive"))
      (node (ref "FB3") (pin "2") (pinfunction "2_2") (pintype "passive"))
      (node (ref "R20") (pin "1") (pinfunction "1_1") (pintype "passive"))
      (node (ref "R21") (pin "1") (pinfunction "1_1") (pintype "passive"))
      (node (ref "R22") (pin "1") (pinfunction "1_1") (pintype "passive"))
      (node (ref "R23") (pin "1") (pinfunction "1_1") (pintype "passive"))
      (node (ref "R24") (pin "1") (pinfunction "1_1") (pintype "passive"))
      (node (ref "R25") (pin "1") (pinfunction "1_1") (pintype "passive"))
    )
    (net (code "146") (name "unconnected-(U4-ID-Pad3)") (class "Default")
      (node (ref "U4") (pin "3") (pinfunction "ID_3") (pintype "passive+no_connect"))
    )
    (net (code "147") (name "unconnected-(U4-NC-Pad5)") (class "Default")
      (node (ref "U4") (pin "5") (pinfunction "NC_5") (pintype "passive+no_connect"))
    )
  )
)
